# gpxtendo_rev2.net
KiCad netlist of a schematic drawn in EAGLE
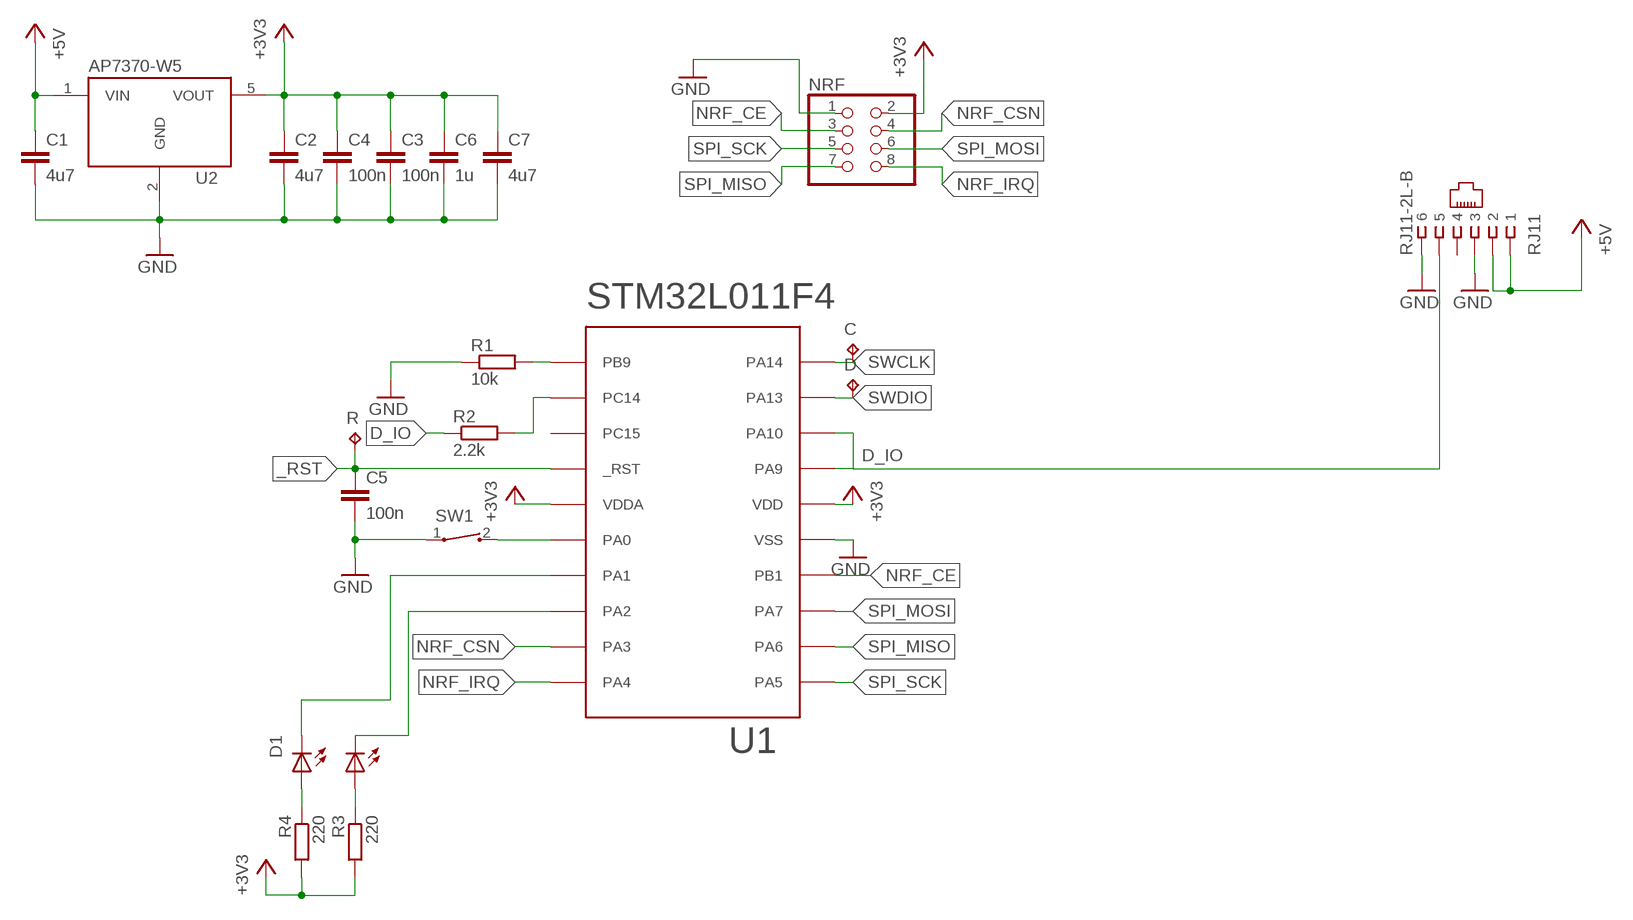
[diagram p0: schematic, sheet 1]

(export (version "E")
  (design (tool "Eeschema 10.0.6"))
  (components
    (comp (ref "C")
      (value "TPTP10R")
      (footprint "eagle-import:TP10R")
      (libsource (lib "eagle-import") (part "TPTP10R"))
    )
    (comp (ref "C1")
      (value "4u7")
      (footprint "eagle-import:C0603-S")
      (libsource (lib "eagle-import") (part "C0603-S"))
    )
    (comp (ref "C2")
      (value "4u7")
      (footprint "eagle-import:C0603-S")
      (libsource (lib "eagle-import") (part "C0603-S"))
    )
    (comp (ref "C3")
      (value "100n")
      (footprint "eagle-import:C0603-S")
      (libsource (lib "eagle-import") (part "C0603-S"))
    )
    (comp (ref "C4")
      (value "100n")
      (footprint "eagle-import:C0603-S")
      (libsource (lib "eagle-import") (part "C0603-S"))
    )
    (comp (ref "C5")
      (value "100n")
      (footprint "eagle-import:C0603-S")
      (libsource (lib "eagle-import") (part "C0603-S"))
    )
    (comp (ref "C6")
      (value "1u")
      (footprint "eagle-import:C0603-S")
      (libsource (lib "eagle-import") (part "C0603-S"))
    )
    (comp (ref "C7")
      (value "4u7")
      (footprint "eagle-import:C0603-S")
      (libsource (lib "eagle-import") (part "C0603-S"))
    )
    (comp (ref "D")
      (value "TPTP10R")
      (footprint "eagle-import:TP10R")
      (libsource (lib "eagle-import") (part "TPTP10R"))
    )
    (comp (ref "D1")
      (value "LED-DUAL")
      (footprint "eagle-import:LED-1210")
      (libsource (lib "eagle-import") (part "LED-DUAL"))
    )
    (comp (ref "NRF")
      (value "PINHD-2X4")
      (footprint "eagle-import:2X04")
      (libsource (lib "eagle-import") (part "PINHD-2X4"))
    )
    (comp (ref "R")
      (value "TPTP10R")
      (footprint "eagle-import:TP10R")
      (libsource (lib "eagle-import") (part "TPTP10R"))
    )
    (comp (ref "R1")
      (value "10k")
      (footprint "eagle-import:R0603-S")
      (libsource (lib "eagle-import") (part "R0603-S"))
    )
    (comp (ref "R2")
      (value "2.2k")
      (footprint "eagle-import:R0603-S")
      (libsource (lib "eagle-import") (part "R0603-S"))
    )
    (comp (ref "R3")
      (value "220")
      (footprint "eagle-import:R0603-S")
      (libsource (lib "eagle-import") (part "R0603-S"))
    )
    (comp (ref "R4")
      (value "220")
      (footprint "eagle-import:R0603-S")
      (libsource (lib "eagle-import") (part "R0603-S"))
    )
    (comp (ref "RJ11")
      (value "RJ11-2L-B")
      (footprint "eagle-import:RJ11-NO_SHIELD")
      (fields (field (name "MF") "TYCO ELECTRONICS"))
      (libsource (lib "eagle-import") (part "RJ11-2L-B"))
    )
    (comp (ref "SW1")
      (value "SW-SPST")
      (footprint "eagle-import:TL3330")
      (libsource (lib "eagle-import") (part "SW-SPST"))
    )
    (comp (ref "U1")
      (value "STM32L011F4PX")
      (footprint "eagle-import:TSSOP-20")
      (libsource (lib "eagle-import") (part "STM32L011F4PX"))
    )
    (comp (ref "U2")
      (value "AP7370-W5")
      (footprint "eagle-import:SOT23-5")
      (libsource (lib "eagle-import") (part "AP7370-W5"))
    )
  )
  (nets
    (net (code "1") (name "+3V3") (class "Default")
      (node (ref "C2") (pin "1") (pinfunction "1_1") (pintype "passive"))
      (node (ref "C3") (pin "1") (pinfunction "1_1") (pintype "passive"))
      (node (ref "C4") (pin "1") (pinfunction "1_1") (pintype "passive"))
      (node (ref "C6") (pin "1") (pinfunction "1_1") (pintype "passive"))
      (node (ref "C7") (pin "1") (pinfunction "1_1") (pintype "passive"))
      (node (ref "NRF") (pin "2") (pinfunction "2_2") (pintype "passive"))
      (node (ref "R3") (pin "2") (pinfunction "2_2") (pintype "passive"))
      (node (ref "R4") (pin "2") (pinfunction "2_2") (pintype "passive"))
      (node (ref "U1") (pin "P$16") (pinfunction "VDD_P$16") (pintype "power_in"))
      (node (ref "U1") (pin "P$5") (pinfunction "VDDA_P$5") (pintype "power_in"))
      (node (ref "U2") (pin "5") (pinfunction "VOUT_5") (pintype "bidirectional"))
    )
    (net (code "2") (name "+5V") (class "Default")
      (node (ref "C1") (pin "1") (pinfunction "1_1") (pintype "passive"))
      (node (ref "RJ11") (pin "1") (pinfunction "1_1") (pintype "passive"))
      (node (ref "RJ11") (pin "2") (pinfunction "2_2") (pintype "passive"))
      (node (ref "U2") (pin "1") (pinfunction "VIN_1") (pintype "bidirectional"))
    )
    (net (code "3") (name "D_IO") (class "Default")
      (node (ref "R2") (pin "1") (pinfunction "1_1") (pintype "passive"))
      (node (ref "RJ11") (pin "5") (pinfunction "5_5") (pintype "passive"))
      (node (ref "U1") (pin "P$17") (pinfunction "PA9_P$17") (pintype "bidirectional"))
      (node (ref "U1") (pin "P$18") (pinfunction "PA10_P$18") (pintype "bidirectional"))
    )
    (net (code "4") (name "GND") (class "Default")
      (node (ref "C1") (pin "2") (pinfunction "2_2") (pintype "passive"))
      (node (ref "C2") (pin "2") (pinfunction "2_2") (pintype "passive"))
      (node (ref "C3") (pin "2") (pinfunction "2_2") (pintype "passive"))
      (node (ref "C4") (pin "2") (pinfunction "2_2") (pintype "passive"))
      (node (ref "C5") (pin "2") (pinfunction "2_2") (pintype "passive"))
      (node (ref "C6") (pin "2") (pinfunction "2_2") (pintype "passive"))
      (node (ref "C7") (pin "2") (pinfunction "2_2") (pintype "passive"))
      (node (ref "NRF") (pin "1") (pinfunction "1_1") (pintype "passive"))
      (node (ref "R1") (pin "1") (pinfunction "1_1") (pintype "passive"))
      (node (ref "RJ11") (pin "3") (pinfunction "3_3") (pintype "passive"))
      (node (ref "RJ11") (pin "6") (pinfunction "6_6") (pintype "passive"))
      (node (ref "SW1") (pin "1") (pinfunction "1_1") (pintype "passive"))
      (node (ref "U1") (pin "P$15") (pinfunction "VSS_P$15") (pintype "power_in"))
      (node (ref "U2") (pin "2") (pinfunction "GND_2") (pintype "bidirectional"))
    )
    (net (code "5") (name "NRF_CE") (class "Default")
      (node (ref "NRF") (pin "3") (pinfunction "3_3") (pintype "passive"))
      (node (ref "U1") (pin "P$14") (pinfunction "PB1_P$14") (pintype "bidirectional"))
    )
    (net (code "6") (name "NRF_CSN") (class "Default")
      (node (ref "NRF") (pin "4") (pinfunction "4_4") (pintype "passive"))
      (node (ref "U1") (pin "P$9") (pinfunction "PA3_P$9") (pintype "bidirectional"))
    )
    (net (code "7") (name "NRF_IRQ") (class "Default")
      (node (ref "NRF") (pin "8") (pinfunction "8_8") (pintype "passive"))
      (node (ref "U1") (pin "P$10") (pinfunction "PA4_P$10") (pintype "bidirectional"))
    )
    (net (code "8") (name "Net-(D1-A0)") (class "Default")
      (node (ref "D1") (pin "2") (pinfunction "A0_2") (pintype "passive"))
      (node (ref "R3") (pin "1") (pinfunction "1_1") (pintype "passive"))
    )
    (net (code "9") (name "Net-(D1-A1)") (class "Default")
      (node (ref "D1") (pin "4") (pinfunction "A1_4") (pintype "passive"))
      (node (ref "R4") (pin "1") (pinfunction "1_1") (pintype "passive"))
    )
    (net (code "10") (name "Net-(D1-C0)") (class "Default")
      (node (ref "D1") (pin "1") (pinfunction "C0_1") (pintype "passive"))
      (node (ref "U1") (pin "P$8") (pinfunction "PA2_P$8") (pintype "bidirectional"))
    )
    (net (code "11") (name "Net-(D1-C1)") (class "Default")
      (node (ref "D1") (pin "3") (pinfunction "C1_3") (pintype "passive"))
      (node (ref "U1") (pin "P$7") (pinfunction "PA1_P$7") (pintype "bidirectional"))
    )
    (net (code "12") (name "Net-(U1-PA0)") (class "Default")
      (node (ref "SW1") (pin "2") (pinfunction "2_2") (pintype "passive"))
      (node (ref "U1") (pin "P$6") (pinfunction "PA0_P$6") (pintype "bidirectional"))
    )
    (net (code "13") (name "Net-(U1-PB9)") (class "Default")
      (node (ref "R1") (pin "2") (pinfunction "2_2") (pintype "passive"))
      (node (ref "U1") (pin "P$1") (pinfunction "PB9_P$1") (pintype "bidirectional"))
    )
    (net (code "14") (name "Net-(U1-PC14)") (class "Default")
      (node (ref "R2") (pin "2") (pinfunction "2_2") (pintype "passive"))
      (node (ref "U1") (pin "P$2") (pinfunction "PC14_P$2") (pintype "bidirectional"))
    )
    (net (code "15") (name "SPI_MISO") (class "Default")
      (node (ref "NRF") (pin "7") (pinfunction "7_7") (pintype "passive"))
      (node (ref "U1") (pin "P$12") (pinfunction "PA6_P$12") (pintype "bidirectional"))
    )
    (net (code "16") (name "SPI_MOSI") (class "Default")
      (node (ref "NRF") (pin "6") (pinfunction "6_6") (pintype "passive"))
      (node (ref "U1") (pin "P$13") (pinfunction "PA7_P$13") (pintype "bidirectional"))
    )
    (net (code "17") (name "SPI_SCK") (class "Default")
      (node (ref "NRF") (pin "5") (pinfunction "5_5") (pintype "passive"))
      (node (ref "U1") (pin "P$11") (pinfunction "PA5_P$11") (pintype "bidirectional"))
    )
    (net (code "18") (name "SWCLK") (class "Default")
      (node (ref "C") (pin "TP") (pinfunction "TP_TP") (pintype "input"))
      (node (ref "U1") (pin "P$20") (pinfunction "PA14_P$20") (pintype "bidirectional"))
    )
    (net (code "19") (name "SWDIO") (class "Default")
      (node (ref "D") (pin "TP") (pinfunction "TP_TP") (pintype "input"))
      (node (ref "U1") (pin "P$19") (pinfunction "PA13_P$19") (pintype "bidirectional"))
    )
    (net (code "20") (name "_RST") (class "Default")
      (node (ref "C5") (pin "1") (pinfunction "1_1") (pintype "passive"))
      (node (ref "R") (pin "TP") (pinfunction "TP_TP") (pintype "input"))
      (node (ref "U1") (pin "P$4") (pinfunction "_RST_P$4") (pintype "bidirectional"))
    )
    (net (code "21") (name "unconnected-(RJ11-Pad4)") (class "Default")
      (node (ref "RJ11") (pin "4") (pinfunction "4_4") (pintype "passive"))
    )
    (net (code "22") (name "unconnected-(U1-PC15-PadP$3)") (class "Default")
      (node (ref "U1") (pin "P$3") (pinfunction "PC15_P$3") (pintype "bidirectional"))
    )
  )
)
